# 1_EVB-A32S1-M_Power.net
KiCad netlist of a schematic drawn in Altium Designer
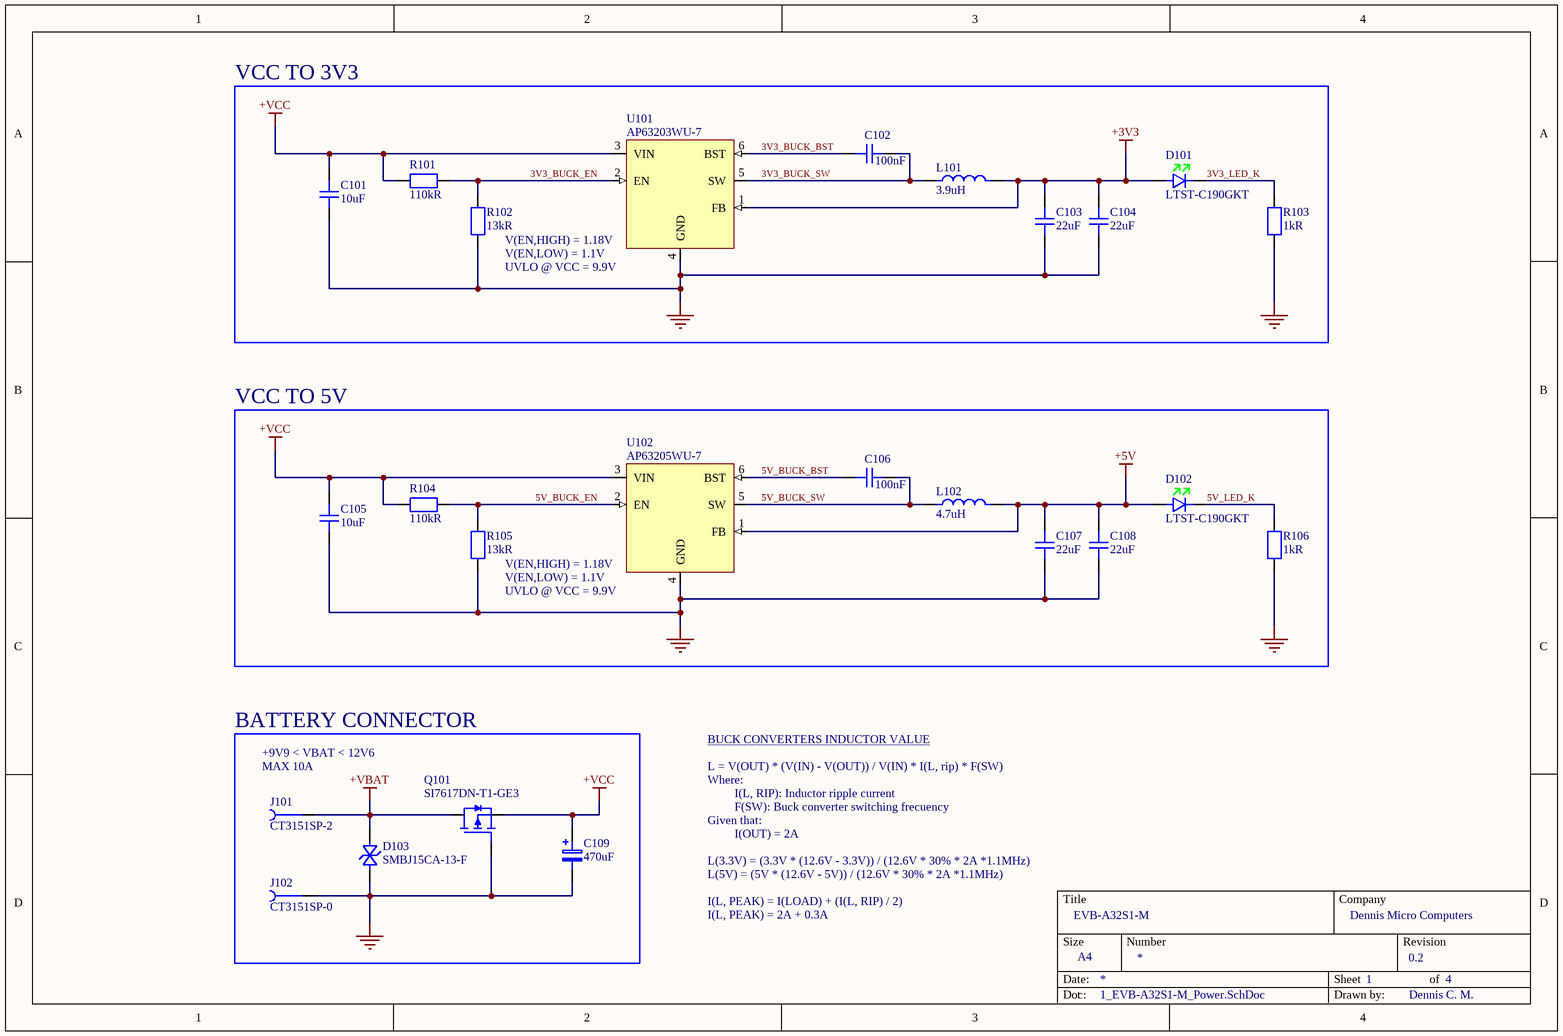
[diagram p0: 1_EVB-A32S1-M_Power.SchDoc]

(export (version "E")
  (design (tool "Eeschema 10.0.6"))
  (components
    (comp (ref "C101")
      (value "10uF")
      (footprint "C_Samsung_CL_0805_A")
      (description "Multilayer Ceramic Capacitor, 10 uF, 16 V, ± 10%, X5R, 0805 [2012 Metric]")
      (fields (field (name "VOLTAGE") "16V") (field (name "TOLERANCE") "10%"))
      (libsource (lib "Dennis Micro Computers") (part "C"))
    )
    (comp (ref "C102")
      (value "100nF")
      (footprint "C_Samsung_CL_0402_A")
      (description "Multilayer Ceramic Capacitor, 0.1 uF, 10 V, ± 10%, X7R, 0402 [1005 Metric]")
      (fields (field (name "TOLERANCE") "10%") (field (name "Comment") "CL05B104KP5NNNC"))
      (libsource (lib "Dennis Micro Computers") (part "C"))
    )
    (comp (ref "C103")
      (value "22uF")
      (footprint "C_Yageo_CC_0805_A")
      (description "Multilayer Ceramic Capacitor, 22 uF, 10 V, ± 20%, X5R, 0805 [2012 Metric]")
      (fields (field (name "TOLERANCE") "20%") (field (name "Comment") "CC0805MKX5R6BB226"))
      (libsource (lib "Dennis Micro Computers") (part "C"))
    )
    (comp (ref "C104")
      (value "22uF")
      (footprint "C_Yageo_CC_0805_A")
      (description "Multilayer Ceramic Capacitor, 22 uF, 10 V, ± 20%, X5R, 0805 [2012 Metric]")
      (fields (field (name "TOLERANCE") "20%") (field (name "Comment") "CC0805MKX5R6BB226"))
      (libsource (lib "Dennis Micro Computers") (part "C"))
    )
    (comp (ref "C105")
      (value "10uF")
      (footprint "C_Samsung_CL_0805_A")
      (description "Multilayer Ceramic Capacitor, 10 uF, 16 V, ± 10%, X5R, 0805 [2012 Metric]")
      (fields (field (name "VOLTAGE") "16V") (field (name "TOLERANCE") "10%"))
      (libsource (lib "Dennis Micro Computers") (part "C"))
    )
    (comp (ref "C106")
      (value "100nF")
      (footprint "C_Samsung_CL_0402_A")
      (description "Multilayer Ceramic Capacitor, 0.1 uF, 10 V, ± 10%, X7R, 0402 [1005 Metric]")
      (fields (field (name "TOLERANCE") "10%") (field (name "Comment") "CL05B104KP5NNNC"))
      (libsource (lib "Dennis Micro Computers") (part "C"))
    )
    (comp (ref "C107")
      (value "22uF")
      (footprint "C_Yageo_CC_0805_A")
      (description "Multilayer Ceramic Capacitor, 22 uF, 10 V, ± 20%, X5R, 0805 [2012 Metric]")
      (fields (field (name "TOLERANCE") "20%") (field (name "Comment") "CC0805MKX5R6BB226"))
      (libsource (lib "Dennis Micro Computers") (part "C"))
    )
    (comp (ref "C108")
      (value "22uF")
      (footprint "C_Yageo_CC_0805_A")
      (description "Multilayer Ceramic Capacitor, 22 uF, 10 V, ± 20%, X5R, 0805 [2012 Metric]")
      (fields (field (name "TOLERANCE") "20%") (field (name "Comment") "CC0805MKX5R6BB226"))
      (libsource (lib "Dennis Micro Computers") (part "C"))
    )
    (comp (ref "C109")
      (value "470uF")
      (footprint "C_Rubycon_10x16mm_TH")
      (description "Cap Aluminum 470uF 35V 20% (10 X 16mm) Radial 5mm 1760mA 10000h 105 C Bulk")
      (fields (field (name "TOLERANCE") "20%") (field (name "VOLTAGE") "35V"))
      (libsource (lib "Dennis Micro Computers") (part "C_Polarized"))
    )
    (comp (ref "D101")
      (value "LTST-C190GKT")
      (footprint "D_LED_Lite-On_Green_0603_A")
      (description "LED Uni-Color Green 565nm 2-Pin Chip LED T/R")
      (fields (field (name "VOLTAGE") "2V"))
      (libsource (lib "Dennis Micro Computers") (part "D_LED_Green"))
    )
    (comp (ref "D102")
      (value "LTST-C190GKT")
      (footprint "D_LED_Lite-On_Green_0603_A")
      (description "LED Uni-Color Green 565nm 2-Pin Chip LED T/R")
      (fields (field (name "VOLTAGE") "2V"))
      (libsource (lib "Dennis Micro Computers") (part "D_LED_Green"))
    )
    (comp (ref "D103")
      (value "SMBJ15CA-13-F")
      (footprint "D_TVS_BI_Diodes_SMBJ15CA-13-F_A")
      (description "Tvs Diode, Bidir, 15V, 600W, Do-214Aa Rohs Compliant: Yes")
      (libsource (lib "Dennis Micro Computers") (part "D_TVS_Bi"))
    )
    (comp (ref "J101")
      (value "CT3151SP-2")
      (footprint "J_CalTest_CT3151SP-2")
      (description "Conn 4mm Safety Banana Jack F 1 POS Solder RA Thru-Hole 1 Port Bag")
      (libsource (lib "Dennis Micro Computers") (part "J_01x01_Socket"))
    )
    (comp (ref "J102")
      (value "CT3151SP-0")
      (footprint "J_CalTest_CT3151SP-0")
      (description "Conn 4mm Safety Banana Jack F 1 POS Solder RA Thru-Hole 1 Port Bag")
      (libsource (lib "Dennis Micro Computers") (part "J_01x01_Socket"))
    )
    (comp (ref "L101")
      (value "3.9uH")
      (footprint "L_Murata_1255AY-XXXX=P3")
      (description "Inductor Power Shielded Wirewound 3.9uH 30% 100KHz Ferrite 4.2A 0.0264Ohm DCR 2424 T/R")
      (fields (field (name "TOLERANCE") "30%") (field (name "Comment") "1255AY-3R9N=P3"))
      (libsource (lib "Dennis Micro Computers") (part "L"))
    )
    (comp (ref "L102")
      (value "4.7uH")
      (footprint "L_Murata_1255AY-XXXX=P3")
      (description "Inductor Power Shielded Wirewound 4.7uH 20% 100KHz Ferrite 4A 0.0276Ohm DCR 2424 T/R")
      (fields (field (name "TOLERANCE") "20%") (field (name "Comment") "1255AY-4R7M=P3"))
      (libsource (lib "Dennis Micro Computers") (part "L"))
    )
    (comp (ref "Q101")
      (value "SI7617DN-T1-GE3")
      (footprint "Q_Vishay_PowerPACK-1212-8")
      (libsource (lib "Dennis Micro Computers") (part "Q_PMOS"))
    )
    (comp (ref "R101")
      (value "110kR")
      (footprint "R_Yageo_RCL_0402_A")
      (description "SMD Chip Resistor, 110 kOhm, ± 1%, 63 mW, 0402 [1005 Metric], Thick Film, General Purpose")
      (fields (field (name "TOLERANCE") "1%") (field (name "Comment") "RC0402FR-07110KL"))
      (libsource (lib "Dennis Micro Computers") (part "R"))
    )
    (comp (ref "R102")
      (value "13kR")
      (footprint "R_Yageo_RCL_0402_A")
      (description "SMD Chip Resistor, 13 kOhm, ± 1%, 63 mW, 0402 [1005 Metric], Thick Film, General Purpose")
      (fields (field (name "TOLERANCE") "1%") (field (name "Comment") "RC0402FR-0713KL"))
      (libsource (lib "Dennis Micro Computers") (part "R"))
    )
    (comp (ref "R103")
      (value "1kR")
      (footprint "R_Yageo_RCL_0402_A")
      (description "SMD Chip Resistor, 1 kOhm, ± 1%, 62.5 mW, 0402 [1005 Metric], Thick Film, General Purpose")
      (fields (field (name "TOLERANCE") "1%") (field (name "Comment") "RC0402FR-071KL"))
      (libsource (lib "Dennis Micro Computers") (part "R"))
    )
    (comp (ref "R104")
      (value "110kR")
      (footprint "R_Yageo_RCL_0402_A")
      (description "SMD Chip Resistor, 110 kOhm, ± 1%, 63 mW, 0402 [1005 Metric], Thick Film, General Purpose")
      (fields (field (name "TOLERANCE") "1%") (field (name "Comment") "RC0402FR-07110KL"))
      (libsource (lib "Dennis Micro Computers") (part "R"))
    )
    (comp (ref "R105")
      (value "13kR")
      (footprint "R_Yageo_RCL_0402_A")
      (description "SMD Chip Resistor, 13 kOhm, ± 1%, 63 mW, 0402 [1005 Metric], Thick Film, General Purpose")
      (fields (field (name "TOLERANCE") "1%") (field (name "Comment") "RC0402FR-0713KL"))
      (libsource (lib "Dennis Micro Computers") (part "R"))
    )
    (comp (ref "R106")
      (value "1kR")
      (footprint "R_Yageo_RCL_0402_A")
      (description "SMD Chip Resistor, 1 kOhm, ± 1%, 62.5 mW, 0402 [1005 Metric], Thick Film, General Purpose")
      (fields (field (name "TOLERANCE") "1%") (field (name "Comment") "RC0402FR-071KL"))
      (libsource (lib "Dennis Micro Computers") (part "R"))
    )
    (comp (ref "U101")
      (value "AP63203WU-7")
      (footprint "U_Diodes_AP623xx")
      (description "AP63203 Series 3.3 V 2 A SMT Fixed Low IQ Synchronous Buck - TSOT-26")
      (libsource (lib "Dennis Micro Computers") (part "U_AP632XX"))
    )
    (comp (ref "U102")
      (value "AP63205WU-7")
      (footprint "U_Diodes_AP623xx")
      (description "AP63205 Series 32 V 2 A 1.1 MHz Synchronous Buck Converter -TSOT-26")
      (libsource (lib "Dennis Micro Computers") (part "U_AP632XX"))
    )
  )
  (nets
    (net (code "1") (name "+3V3") (class "Default")
      (node (ref "C103") (pin "2") (pinfunction "2_2") (pintype "passive"))
      (node (ref "C104") (pin "2") (pinfunction "2_2") (pintype "passive"))
      (node (ref "D101") (pin "2") (pinfunction "2_2") (pintype "passive"))
      (node (ref "L101") (pin "2") (pinfunction "2_2") (pintype "passive"))
      (node (ref "U101") (pin "1") (pinfunction "FB_1") (pintype "input"))
    )
    (net (code "2") (name "+5V") (class "Default")
      (node (ref "C107") (pin "2") (pinfunction "2_2") (pintype "passive"))
      (node (ref "C108") (pin "2") (pinfunction "2_2") (pintype "passive"))
      (node (ref "D102") (pin "2") (pinfunction "2_2") (pintype "passive"))
      (node (ref "L102") (pin "2") (pinfunction "2_2") (pintype "passive"))
      (node (ref "U102") (pin "1") (pinfunction "FB_1") (pintype "input"))
    )
    (net (code "3") (name "+VBAT") (class "Default")
      (node (ref "D103") (pin "1") (pinfunction "1_1") (pintype "passive"))
      (node (ref "J101") (pin "1") (pinfunction "1_1") (pintype "passive"))
      (node (ref "Q101") (pin "1") (pinfunction "D_1") (pintype "passive"))
    )
    (net (code "4") (name "+VCC") (class "Default")
      (node (ref "C101") (pin "2") (pinfunction "2_2") (pintype "passive"))
      (node (ref "C105") (pin "2") (pinfunction "2_2") (pintype "passive"))
      (node (ref "C109") (pin "1") (pinfunction "1_1") (pintype "passive"))
      (node (ref "Q101") (pin "3") (pinfunction "S_3") (pintype "passive"))
      (node (ref "R101") (pin "2") (pinfunction "2_2") (pintype "passive"))
      (node (ref "R104") (pin "2") (pinfunction "2_2") (pintype "passive"))
      (node (ref "U101") (pin "3") (pinfunction "VIN_3") (pintype "power_in"))
      (node (ref "U102") (pin "3") (pinfunction "VIN_3") (pintype "power_in"))
    )
    (net (code "5") (name "/3V3_BUCK_BST") (class "Default")
      (node (ref "C102") (pin "2") (pinfunction "2_2") (pintype "passive"))
      (node (ref "U101") (pin "6") (pinfunction "BST_6") (pintype "input"))
    )
    (net (code "6") (name "/3V3_BUCK_EN") (class "Default")
      (node (ref "R101") (pin "1") (pinfunction "1_1") (pintype "passive"))
      (node (ref "R102") (pin "2") (pinfunction "2_2") (pintype "passive"))
      (node (ref "U101") (pin "2") (pinfunction "EN_2") (pintype "input"))
    )
    (net (code "7") (name "/3V3_BUCK_SW") (class "Default")
      (node (ref "C102") (pin "1") (pinfunction "1_1") (pintype "passive"))
      (node (ref "L101") (pin "1") (pinfunction "1_1") (pintype "passive"))
      (node (ref "U101") (pin "5") (pinfunction "SW_5") (pintype "power_in"))
    )
    (net (code "8") (name "/3V3_LED_K") (class "Default")
      (node (ref "D101") (pin "1") (pinfunction "1_1") (pintype "passive"))
      (node (ref "R103") (pin "2") (pinfunction "2_2") (pintype "passive"))
    )
    (net (code "9") (name "/5V_BUCK_BST") (class "Default")
      (node (ref "C106") (pin "2") (pinfunction "2_2") (pintype "passive"))
      (node (ref "U102") (pin "6") (pinfunction "BST_6") (pintype "input"))
    )
    (net (code "10") (name "/5V_BUCK_EN") (class "Default")
      (node (ref "R104") (pin "1") (pinfunction "1_1") (pintype "passive"))
      (node (ref "R105") (pin "2") (pinfunction "2_2") (pintype "passive"))
      (node (ref "U102") (pin "2") (pinfunction "EN_2") (pintype "input"))
    )
    (net (code "11") (name "/5V_BUCK_SW") (class "Default")
      (node (ref "C106") (pin "1") (pinfunction "1_1") (pintype "passive"))
      (node (ref "L102") (pin "1") (pinfunction "1_1") (pintype "passive"))
      (node (ref "U102") (pin "5") (pinfunction "SW_5") (pintype "power_in"))
    )
    (net (code "12") (name "/5V_LED_K") (class "Default")
      (node (ref "D102") (pin "1") (pinfunction "1_1") (pintype "passive"))
      (node (ref "R106") (pin "2") (pinfunction "2_2") (pintype "passive"))
    )
    (net (code "13") (name "GND") (class "Default")
      (node (ref "C101") (pin "1") (pinfunction "1_1") (pintype "passive"))
      (node (ref "C103") (pin "1") (pinfunction "1_1") (pintype "passive"))
      (node (ref "C104") (pin "1") (pinfunction "1_1") (pintype "passive"))
      (node (ref "C105") (pin "1") (pinfunction "1_1") (pintype "passive"))
      (node (ref "C107") (pin "1") (pinfunction "1_1") (pintype "passive"))
      (node (ref "C108") (pin "1") (pinfunction "1_1") (pintype "passive"))
      (node (ref "C109") (pin "2") (pinfunction "2_2") (pintype "passive"))
      (node (ref "D103") (pin "2") (pinfunction "2_2") (pintype "passive"))
      (node (ref "J102") (pin "1") (pinfunction "1_1") (pintype "passive"))
      (node (ref "Q101") (pin "2") (pinfunction "G_2") (pintype "passive"))
      (node (ref "R102") (pin "1") (pinfunction "1_1") (pintype "passive"))
      (node (ref "R103") (pin "1") (pinfunction "1_1") (pintype "passive"))
      (node (ref "R105") (pin "1") (pinfunction "1_1") (pintype "passive"))
      (node (ref "R106") (pin "1") (pinfunction "1_1") (pintype "passive"))
      (node (ref "U101") (pin "4") (pinfunction "GND_4") (pintype "power_in"))
      (node (ref "U102") (pin "4") (pinfunction "GND_4") (pintype "power_in"))
    )
  )
)
